# Robot2.net
KiCad netlist of a schematic drawn in EAGLE
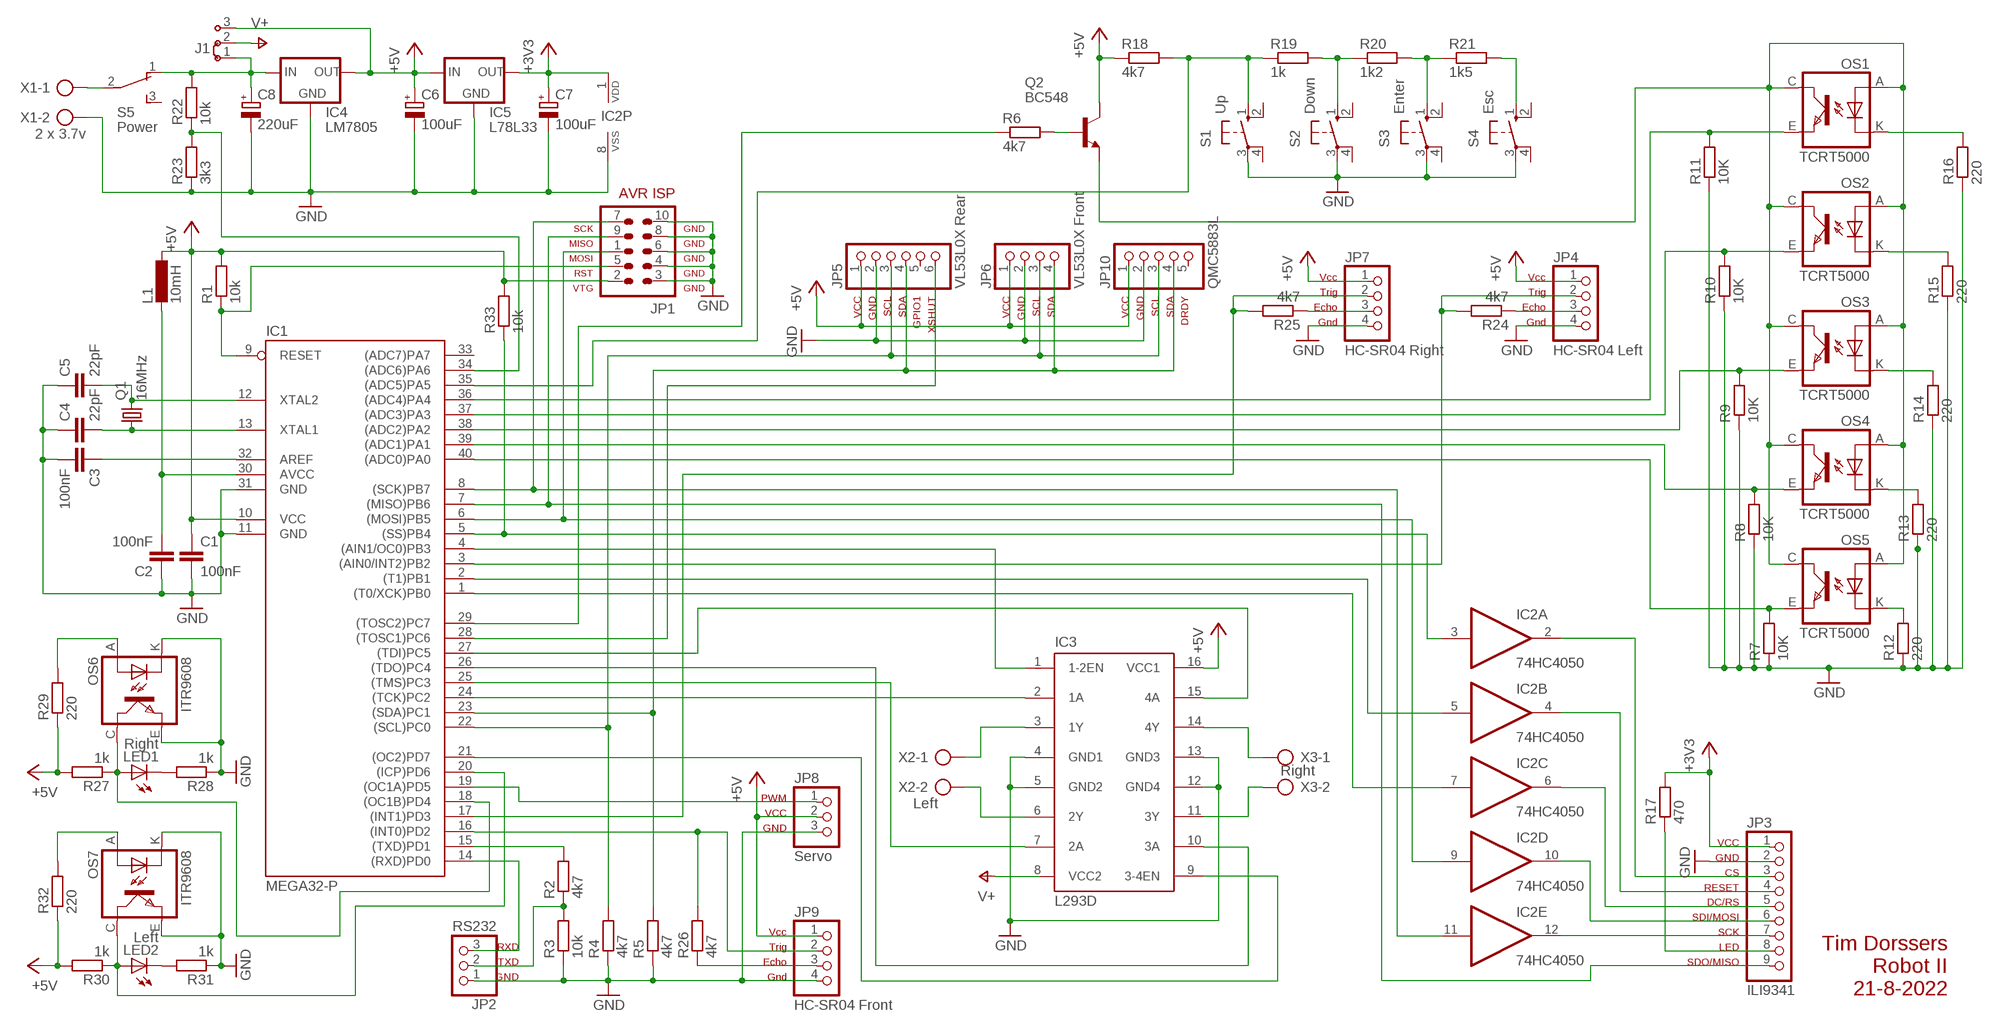
[diagram p0: schematic, sheet 1]

(export (version "E")
  (design (tool "Eeschema 10.0.6"))
  (components
    (comp (ref "C1")
      (value "100nF")
      (footprint "eagle-import:C050-025X075")
      (libsource (lib "eagle-import") (part "C-EU050-025X075"))
    )
    (comp (ref "C2")
      (value "100nF")
      (footprint "eagle-import:C050-025X075")
      (libsource (lib "eagle-import") (part "C-EU050-025X075"))
    )
    (comp (ref "C3")
      (value "100nF")
      (footprint "eagle-import:C050-025X075")
      (libsource (lib "eagle-import") (part "C-EU050-025X075"))
    )
    (comp (ref "C4")
      (value "22pF")
      (footprint "eagle-import:C025-024X044")
      (libsource (lib "eagle-import") (part "C-EU025-024X044"))
    )
    (comp (ref "C5")
      (value "22pF")
      (footprint "eagle-import:C025-024X044")
      (libsource (lib "eagle-import") (part "C-EU025-024X044"))
    )
    (comp (ref "C6")
      (value "100uF")
      (footprint "eagle-import:B45181A")
      (libsource (lib "eagle-import") (part "CPOL-EUB45181A"))
    )
    (comp (ref "C7")
      (value "100uF")
      (footprint "eagle-import:B45181A")
      (libsource (lib "eagle-import") (part "CPOL-EUB45181A"))
    )
    (comp (ref "C8")
      (value "220uF")
      (footprint "eagle-import:B45181A")
      (libsource (lib "eagle-import") (part "CPOL-EUB45181A"))
    )
    (comp (ref "IC1")
      (value "MEGA32-P")
      (footprint "eagle-import:DIL40")
      (fields (field (name "MPN") "ATMEGA32-16PU"))
      (libsource (lib "eagle-import") (part "MEGA32-P"))
    )
    (comp (ref "IC2")
      (value "74HC4050")
      (footprint "eagle-import:DIL16")
      (libsource (lib "eagle-import") (part "4050N"))
    )
    (comp (ref "IC3")
      (value "L293D")
      (footprint "eagle-import:DIL16")
      (libsource (lib "eagle-import") (part "L293D"))
    )
    (comp (ref "IC4")
      (value "LM7805")
      (footprint "eagle-import:78XXL")
      (libsource (lib "eagle-import") (part "78XXL"))
    )
    (comp (ref "IC5")
      (value "L78L33")
      (footprint "eagle-import:78LXX")
      (libsource (lib "eagle-import") (part "78LXX"))
    )
    (comp (ref "J1")
      (value "J2X2MM")
      (footprint "eagle-import:04C")
      (libsource (lib "eagle-import") (part "J2X2MM"))
    )
    (comp (ref "JP1")
      (value "AVR-ISP-10")
      (footprint "eagle-import:AVR-ISP-10")
      (libsource (lib "eagle-import") (part "AVR-ISP-10"))
    )
    (comp (ref "JP2")
      (value "RS232")
      (footprint "eagle-import:1X03")
      (libsource (lib "eagle-import") (part "PINHD-1X3"))
    )
    (comp (ref "JP3")
      (value "ILI9341")
      (footprint "eagle-import:1X09")
      (libsource (lib "eagle-import") (part "PINHD-1X9"))
    )
    (comp (ref "JP4")
      (value "HC-SR04 Left")
      (footprint "eagle-import:1X04")
      (libsource (lib "eagle-import") (part "PINHD-1X4"))
    )
    (comp (ref "JP5")
      (value "VL53L0X Rear")
      (footprint "eagle-import:1X06")
      (libsource (lib "eagle-import") (part "PINHD-1X6"))
    )
    (comp (ref "JP6")
      (value "VL53L0X Front")
      (footprint "eagle-import:1X04")
      (libsource (lib "eagle-import") (part "PINHD-1X4"))
    )
    (comp (ref "JP7")
      (value "HC-SR04 Right")
      (footprint "eagle-import:1X04")
      (libsource (lib "eagle-import") (part "PINHD-1X4"))
    )
    (comp (ref "JP8")
      (value "Servo")
      (footprint "eagle-import:1X03")
      (libsource (lib "eagle-import") (part "PINHD-1X3"))
    )
    (comp (ref "JP9")
      (value "HC-SR04 Front")
      (footprint "eagle-import:1X04")
      (libsource (lib "eagle-import") (part "PINHD-1X4"))
    )
    (comp (ref "JP10")
      (value "QMC5883L")
      (footprint "eagle-import:1X05")
      (libsource (lib "eagle-import") (part "PINHD-1X5"))
    )
    (comp (ref "L1")
      (value "10mH")
      (footprint "eagle-import:0207_10")
      (libsource (lib "eagle-import") (part "L-EU0207/10"))
    )
    (comp (ref "LED1")
      (value "Right")
      (footprint "eagle-import:LED5MM")
      (libsource (lib "eagle-import") (part "LED5MM"))
    )
    (comp (ref "LED2")
      (value "Left")
      (footprint "eagle-import:LED5MM")
      (libsource (lib "eagle-import") (part "LED5MM"))
    )
    (comp (ref "OS1")
      (value "TCRT5000")
      (footprint "eagle-import:TCRT5000")
      (libsource (lib "eagle-import") (part "TCRT5000"))
    )
    (comp (ref "OS2")
      (value "TCRT5000")
      (footprint "eagle-import:TCRT5000")
      (libsource (lib "eagle-import") (part "TCRT5000"))
    )
    (comp (ref "OS3")
      (value "TCRT5000")
      (footprint "eagle-import:TCRT5000")
      (libsource (lib "eagle-import") (part "TCRT5000"))
    )
    (comp (ref "OS4")
      (value "TCRT5000")
      (footprint "eagle-import:TCRT5000")
      (libsource (lib "eagle-import") (part "TCRT5000"))
    )
    (comp (ref "OS5")
      (value "TCRT5000")
      (footprint "eagle-import:TCRT5000")
      (libsource (lib "eagle-import") (part "TCRT5000"))
    )
    (comp (ref "OS6")
      (value "ITR9608")
      (footprint "eagle-import:TCRT5000")
      (libsource (lib "eagle-import") (part "TCRT5000"))
    )
    (comp (ref "OS7")
      (value "ITR9608")
      (footprint "eagle-import:TCRT5000")
      (libsource (lib "eagle-import") (part "TCRT5000"))
    )
    (comp (ref "Q1")
      (value "16MHz")
      (footprint "eagle-import:HC49U-V")
      (libsource (lib "eagle-import") (part "CRYSTALHC49U-V"))
    )
    (comp (ref "Q2")
      (value "BC548")
      (footprint "eagle-import:TO92-EBC")
      (libsource (lib "eagle-import") (part "BC548"))
    )
    (comp (ref "R1")
      (value "10k")
      (footprint "eagle-import:0207_2V")
      (libsource (lib "eagle-import") (part "R-EU_0207/2V"))
    )
    (comp (ref "R2")
      (value "4k7")
      (footprint "eagle-import:0207_2V")
      (libsource (lib "eagle-import") (part "R-EU_0207/2V"))
    )
    (comp (ref "R3")
      (value "10k")
      (footprint "eagle-import:0207_2V")
      (libsource (lib "eagle-import") (part "R-EU_0207/2V"))
    )
    (comp (ref "R4")
      (value "4k7")
      (footprint "eagle-import:0207_2V")
      (libsource (lib "eagle-import") (part "R-EU_0207/2V"))
    )
    (comp (ref "R5")
      (value "4k7")
      (footprint "eagle-import:0207_2V")
      (libsource (lib "eagle-import") (part "R-EU_0207/2V"))
    )
    (comp (ref "R6")
      (value "4k7")
      (footprint "eagle-import:0207_2V")
      (libsource (lib "eagle-import") (part "R-EU_0207/2V"))
    )
    (comp (ref "R7")
      (value "10K")
      (footprint "eagle-import:0204_7")
      (libsource (lib "eagle-import") (part "resistor_R-EU_0204/7"))
    )
    (comp (ref "R8")
      (value "10K")
      (footprint "eagle-import:0204_7")
      (libsource (lib "eagle-import") (part "resistor_R-EU_0204/7"))
    )
    (comp (ref "R9")
      (value "10K")
      (footprint "eagle-import:0204_7")
      (libsource (lib "eagle-import") (part "resistor_R-EU_0204/7"))
    )
    (comp (ref "R10")
      (value "10K")
      (footprint "eagle-import:0204_7")
      (libsource (lib "eagle-import") (part "resistor_R-EU_0204/7"))
    )
    (comp (ref "R11")
      (value "10K")
      (footprint "eagle-import:0204_7")
      (libsource (lib "eagle-import") (part "resistor_R-EU_0204/7"))
    )
    (comp (ref "R12")
      (value "220")
      (footprint "eagle-import:0204_7")
      (libsource (lib "eagle-import") (part "resistor_R-EU_0204/7"))
    )
    (comp (ref "R13")
      (value "220")
      (footprint "eagle-import:0204_7")
      (libsource (lib "eagle-import") (part "resistor_R-EU_0204/7"))
    )
    (comp (ref "R14")
      (value "220")
      (footprint "eagle-import:0204_7")
      (libsource (lib "eagle-import") (part "resistor_R-EU_0204/7"))
    )
    (comp (ref "R15")
      (value "220")
      (footprint "eagle-import:0204_7")
      (libsource (lib "eagle-import") (part "resistor_R-EU_0204/7"))
    )
    (comp (ref "R16")
      (value "220")
      (footprint "eagle-import:0204_7")
      (libsource (lib "eagle-import") (part "resistor_R-EU_0204/7"))
    )
    (comp (ref "R17")
      (value "470")
      (footprint "eagle-import:0207_2V")
      (libsource (lib "eagle-import") (part "R-EU_0207/2V"))
    )
    (comp (ref "R18")
      (value "4k7")
      (footprint "eagle-import:0207_2V")
      (libsource (lib "eagle-import") (part "R-EU_0207/2V"))
    )
    (comp (ref "R19")
      (value "1k")
      (footprint "eagle-import:0207_2V")
      (libsource (lib "eagle-import") (part "R-EU_0207/2V"))
    )
    (comp (ref "R20")
      (value "1k2")
      (footprint "eagle-import:0207_2V")
      (libsource (lib "eagle-import") (part "R-EU_0207/2V"))
    )
    (comp (ref "R21")
      (value "1k5")
      (footprint "eagle-import:0207_2V")
      (libsource (lib "eagle-import") (part "R-EU_0207/2V"))
    )
    (comp (ref "R22")
      (value "10k")
      (footprint "eagle-import:0207_2V")
      (libsource (lib "eagle-import") (part "R-EU_0207/2V"))
    )
    (comp (ref "R23")
      (value "3k3")
      (footprint "eagle-import:0207_2V")
      (libsource (lib "eagle-import") (part "R-EU_0207/2V"))
    )
    (comp (ref "R24")
      (value "4k7")
      (footprint "eagle-import:0207_2V")
      (libsource (lib "eagle-import") (part "R-EU_0207/2V"))
    )
    (comp (ref "R25")
      (value "4k7")
      (footprint "eagle-import:0207_2V")
      (libsource (lib "eagle-import") (part "R-EU_0207/2V"))
    )
    (comp (ref "R26")
      (value "4k7")
      (footprint "eagle-import:0207_2V")
      (libsource (lib "eagle-import") (part "R-EU_0207/2V"))
    )
    (comp (ref "R27")
      (value "1k")
      (footprint "eagle-import:0207_2V")
      (libsource (lib "eagle-import") (part "R-EU_0207/2V"))
    )
    (comp (ref "R28")
      (value "1k")
      (footprint "eagle-import:0207_2V")
      (libsource (lib "eagle-import") (part "R-EU_0207/2V"))
    )
    (comp (ref "R29")
      (value "220")
      (footprint "eagle-import:0207_2V")
      (libsource (lib "eagle-import") (part "R-EU_0207/2V"))
    )
    (comp (ref "R30")
      (value "1k")
      (footprint "eagle-import:0207_2V")
      (libsource (lib "eagle-import") (part "R-EU_0207/2V"))
    )
    (comp (ref "R31")
      (value "1k")
      (footprint "eagle-import:0207_2V")
      (libsource (lib "eagle-import") (part "R-EU_0207/2V"))
    )
    (comp (ref "R32")
      (value "220")
      (footprint "eagle-import:0207_2V")
      (libsource (lib "eagle-import") (part "R-EU_0207/2V"))
    )
    (comp (ref "R33")
      (value "10k")
      (footprint "eagle-import:0207_2V")
      (libsource (lib "eagle-import") (part "R-EU_0207/2V"))
    )
    (comp (ref "S1")
      (value "Up")
      (footprint "eagle-import:B3F-10XX")
      (fields (field (name "MPN") "B3F-1000"))
      (libsource (lib "eagle-import") (part "10-XX"))
    )
    (comp (ref "S2")
      (value "Down")
      (footprint "eagle-import:B3F-10XX")
      (fields (field (name "MPN") "B3F-1000"))
      (libsource (lib "eagle-import") (part "10-XX"))
    )
    (comp (ref "S3")
      (value "Enter")
      (footprint "eagle-import:B3F-10XX")
      (fields (field (name "MPN") "B3F-1000"))
      (libsource (lib "eagle-import") (part "10-XX"))
    )
    (comp (ref "S4")
      (value "Esc")
      (footprint "eagle-import:B3F-10XX")
      (fields (field (name "MPN") "B3F-1000"))
      (libsource (lib "eagle-import") (part "10-XX"))
    )
    (comp (ref "S5")
      (value "Power")
      (footprint "eagle-import:TL3XPO")
      (libsource (lib "eagle-import") (part "TL36PO"))
    )
    (comp (ref "X1")
      (value "2 x 3.7v")
      (footprint "eagle-import:AK300_2")
      (libsource (lib "eagle-import") (part "AK300/2"))
    )
    (comp (ref "X2")
      (value "Left")
      (footprint "eagle-import:AK300_2")
      (libsource (lib "eagle-import") (part "AK300/2"))
    )
    (comp (ref "X3")
      (value "Right")
      (footprint "eagle-import:AK300_2")
      (libsource (lib "eagle-import") (part "AK300/2"))
    )
  )
  (nets
    (net (code "1") (name "+3V3") (class "Default")
      (node (ref "C7") (pin "+") (pinfunction "+_+") (pintype "passive"))
      (node (ref "IC2") (pin "1") (pinfunction "VDD_1") (pintype "power_in"))
      (node (ref "IC5") (pin "OUT") (pinfunction "OUT_OUT") (pintype "passive"))
      (node (ref "JP3") (pin "1") (pinfunction "1_1") (pintype "passive"))
      (node (ref "R17") (pin "2") (pinfunction "2_2") (pintype "passive"))
    )
    (net (code "2") (name "+5V") (class "Default")
      (node (ref "C1") (pin "1") (pinfunction "1_1") (pintype "passive"))
      (node (ref "C6") (pin "+") (pinfunction "+_+") (pintype "passive"))
      (node (ref "IC1") (pin "10") (pinfunction "VCC_10") (pintype "power_in"))
      (node (ref "IC3") (pin "16") (pinfunction "VCC1_16") (pintype "power_in"))
      (node (ref "IC4") (pin "OUT") (pinfunction "OUT_OUT") (pintype "passive"))
      (node (ref "IC5") (pin "IN") (pinfunction "IN_IN") (pintype "input"))
      (node (ref "J1") (pin "3") (pinfunction "3_3") (pintype "passive"))
      (node (ref "JP1") (pin "2") (pinfunction "2_2") (pintype "passive"))
      (node (ref "JP10") (pin "1") (pinfunction "1_1") (pintype "passive"))
      (node (ref "JP4") (pin "1") (pinfunction "1_1") (pintype "passive"))
      (node (ref "JP5") (pin "1") (pinfunction "1_1") (pintype "passive"))
      (node (ref "JP6") (pin "1") (pinfunction "1_1") (pintype "passive"))
      (node (ref "JP7") (pin "1") (pinfunction "1_1") (pintype "passive"))
      (node (ref "JP8") (pin "2") (pinfunction "2_2") (pintype "passive"))
      (node (ref "JP9") (pin "1") (pinfunction "1_1") (pintype "passive"))
      (node (ref "L1") (pin "1") (pinfunction "1_1") (pintype "passive"))
      (node (ref "Q2") (pin "C") (pinfunction "C_C") (pintype "passive"))
      (node (ref "R1") (pin "2") (pinfunction "2_2") (pintype "passive"))
      (node (ref "R18") (pin "1") (pinfunction "1_1") (pintype "passive"))
      (node (ref "R27") (pin "2") (pinfunction "2_2") (pintype "passive"))
      (node (ref "R29") (pin "1") (pinfunction "1_1") (pintype "passive"))
      (node (ref "R30") (pin "2") (pinfunction "2_2") (pintype "passive"))
      (node (ref "R32") (pin "1") (pinfunction "1_1") (pintype "passive"))
      (node (ref "R33") (pin "2") (pinfunction "2_2") (pintype "passive"))
    )
    (net (code "3") (name "/VCC2") (class "Default")
      (node (ref "IC3") (pin "8") (pinfunction "VCC2_8") (pintype "power_in"))
    )
    (net (code "4") (name "GND") (class "Default")
      (node (ref "C1") (pin "2") (pinfunction "2_2") (pintype "passive"))
      (node (ref "C2") (pin "1") (pinfunction "1_1") (pintype "passive"))
      (node (ref "C3") (pin "2") (pinfunction "2_2") (pintype "passive"))
      (node (ref "C4") (pin "1") (pinfunction "1_1") (pintype "passive"))
      (node (ref "C5") (pin "1") (pinfunction "1_1") (pintype "passive"))
      (node (ref "C6") (pin "-") (pinfunction "-_-") (pintype "passive"))
      (node (ref "C7") (pin "-") (pinfunction "-_-") (pintype "passive"))
      (node (ref "C8") (pin "-") (pinfunction "-_-") (pintype "passive"))
      (node (ref "IC1") (pin "11") (pinfunction "GND_11") (pintype "power_in"))
      (node (ref "IC1") (pin "31") (pinfunction "GND_31") (pintype "power_in"))
      (node (ref "IC2") (pin "8") (pinfunction "VSS_8") (pintype "power_in"))
      (node (ref "IC3") (pin "12") (pinfunction "GND4_12") (pintype "power_in"))
      (node (ref "IC3") (pin "13") (pinfunction "GND3_13") (pintype "power_in"))
      (node (ref "IC3") (pin "4") (pinfunction "GND1_4") (pintype "power_in"))
      (node (ref "IC3") (pin "5") (pinfunction "GND2_5") (pintype "power_in"))
      (node (ref "IC4") (pin "GND") (pinfunction "GND_GND") (pintype "input"))
      (node (ref "IC5") (pin "GND") (pinfunction "GND_GND") (pintype "input"))
      (node (ref "JP1") (pin "10") (pinfunction "10_10") (pintype "passive"))
      (node (ref "JP1") (pin "3") (pinfunction "3_3") (pintype "passive"))
      (node (ref "JP1") (pin "4") (pinfunction "4_4") (pintype "passive"))
      (node (ref "JP1") (pin "6") (pinfunction "6_6") (pintype "passive"))
      (node (ref "JP1") (pin "8") (pinfunction "8_8") (pintype "passive"))
      (node (ref "JP10") (pin "2") (pinfunction "2_2") (pintype "passive"))
      (node (ref "JP2") (pin "1") (pinfunction "1_1") (pintype "passive"))
      (node (ref "JP3") (pin "2") (pinfunction "2_2") (pintype "passive"))
      (node (ref "JP4") (pin "4") (pinfunction "4_4") (pintype "passive"))
      (node (ref "JP5") (pin "2") (pinfunction "2_2") (pintype "passive"))
      (node (ref "JP6") (pin "2") (pinfunction "2_2") (pintype "passive"))
      (node (ref "JP7") (pin "4") (pinfunction "4_4") (pintype "passive"))
      (node (ref "JP8") (pin "3") (pinfunction "3_3") (pintype "passive"))
      (node (ref "JP9") (pin "4") (pinfunction "4_4") (pintype "passive"))
      (node (ref "OS6") (pin "E") (pinfunction "EMITTER_E") (pintype "passive"))
      (node (ref "OS6") (pin "K") (pinfunction "CATHODE_K") (pintype "passive"))
      (node (ref "OS7") (pin "E") (pinfunction "EMITTER_E") (pintype "passive"))
      (node (ref "OS7") (pin "K") (pinfunction "CATHODE_K") (pintype "passive"))
      (node (ref "R10") (pin "1") (pinfunction "1_1") (pintype "passive"))
      (node (ref "R11") (pin "1") (pinfunction "1_1") (pintype "passive"))
      (node (ref "R12") (pin "1") (pinfunction "1_1") (pintype "passive"))
      (node (ref "R13") (pin "1") (pinfunction "1_1") (pintype "passive"))
      (node (ref "R14") (pin "1") (pinfunction "1_1") (pintype "passive"))
      (node (ref "R15") (pin "1") (pinfunction "1_1") (pintype "passive"))
      (node (ref "R16") (pin "1") (pinfunction "1_1") (pintype "passive"))
      (node (ref "R23") (pin "1") (pinfunction "1_1") (pintype "passive"))
      (node (ref "R28") (pin "1") (pinfunction "1_1") (pintype "passive"))
      (node (ref "R3") (pin "1") (pinfunction "1_1") (pintype "passive"))
      (node (ref "R31") (pin "1") (pinfunction "1_1") (pintype "passive"))
      (node (ref "R4") (pin "1") (pinfunction "1_1") (pintype "passive"))
      (node (ref "R5") (pin "1") (pinfunction "1_1") (pintype "passive"))
      (node (ref "R7") (pin "1") (pinfunction "1_1") (pintype "passive"))
      (node (ref "R8") (pin "1") (pinfunction "1_1") (pintype "passive"))
      (node (ref "R9") (pin "1") (pinfunction "1_1") (pintype "passive"))
      (node (ref "S1") (pin "3") (pinfunction "P_3") (pintype "passive"))
      (node (ref "S2") (pin "3") (pinfunction "P_3") (pintype "passive"))
      (node (ref "S3") (pin "3") (pinfunction "P_3") (pintype "passive"))
      (node (ref "S4") (pin "3") (pinfunction "P_3") (pintype "passive"))
      (node (ref "X1") (pin "2") (pinfunction "KL_2") (pintype "passive"))
    )
    (net (code "5") (name "Net-(IC1-(ADC0)PA0)") (class "Default")
      (node (ref "IC1") (pin "40") (pinfunction "(ADC0)PA0_40") (pintype "bidirectional"))
      (node (ref "OS5") (pin "E") (pinfunction "EMITTER_E") (pintype "passive"))
      (node (ref "R7") (pin "2") (pinfunction "2_2") (pintype "passive"))
    )
    (net (code "6") (name "Net-(IC1-(ADC1)PA1)") (class "Default")
      (node (ref "IC1") (pin "39") (pinfunction "(ADC1)PA1_39") (pintype "bidirectional"))
      (node (ref "OS4") (pin "E") (pinfunction "EMITTER_E") (pintype "passive"))
      (node (ref "R8") (pin "2") (pinfunction "2_2") (pintype "passive"))
    )
    (net (code "7") (name "Net-(IC1-(ADC2)PA2)") (class "Default")
      (node (ref "IC1") (pin "38") (pinfunction "(ADC2)PA2_38") (pintype "bidirectional"))
      (node (ref "OS3") (pin "E") (pinfunction "EMITTER_E") (pintype "passive"))
      (node (ref "R9") (pin "2") (pinfunction "2_2") (pintype "passive"))
    )
    (net (code "8") (name "Net-(IC1-(ADC3)PA3)") (class "Default")
      (node (ref "IC1") (pin "37") (pinfunction "(ADC3)PA3_37") (pintype "bidirectional"))
      (node (ref "OS2") (pin "E") (pinfunction "EMITTER_E") (pintype "passive"))
      (node (ref "R10") (pin "2") (pinfunction "2_2") (pintype "passive"))
    )
    (net (code "9") (name "Net-(IC1-(ADC4)PA4)") (class "Default")
      (node (ref "IC1") (pin "36") (pinfunction "(ADC4)PA4_36") (pintype "bidirectional"))
      (node (ref "OS1") (pin "E") (pinfunction "EMITTER_E") (pintype "passive"))
      (node (ref "R11") (pin "2") (pinfunction "2_2") (pintype "passive"))
    )
    (net (code "10") (name "Net-(IC1-(ADC5)PA5)") (class "Default")
      (node (ref "IC1") (pin "35") (pinfunction "(ADC5)PA5_35") (pintype "bidirectional"))
      (node (ref "R18") (pin "2") (pinfunction "2_2") (pintype "passive"))
      (node (ref "R19") (pin "1") (pinfunction "1_1") (pintype "passive"))
      (node (ref "S1") (pin "1") (pinfunction "S_1") (pintype "passive"))
    )
    (net (code "11") (name "Net-(IC1-(ADC6)PA6)") (class "Default")
      (node (ref "IC1") (pin "34") (pinfunction "(ADC6)PA6_34") (pintype "bidirectional"))
      (node (ref "R22") (pin "1") (pinfunction "1_1") (pintype "passive"))
      (node (ref "R23") (pin "2") (pinfunction "2_2") (pintype "passive"))
    )
    (net (code "12") (name "Net-(IC1-(AIN0{slash}INT2)PB2)") (class "Default")
      (node (ref "IC1") (pin "3") (pinfunction "(AIN0/INT2)PB2_3") (pintype "bidirectional"))
      (node (ref "JP4") (pin "2") (pinfunction "2_2") (pintype "passive"))
      (node (ref "R24") (pin "2") (pinfunction "2_2") (pintype "passive"))
    )
    (net (code "13") (name "Net-(IC1-(AIN1{slash}OC0)PB3)") (class "Default")
      (node (ref "IC1") (pin "4") (pinfunction "(AIN1/OC0)PB3_4") (pintype "bidirectional"))
      (node (ref "IC3") (pin "1") (pinfunction "1-2EN_1") (pintype "input"))
    )
    (net (code "14") (name "Net-(IC1-(ICP)PD6)") (class "Default")
      (node (ref "IC1") (pin "20") (pinfunction "(ICP)PD6_20") (pintype "bidirectional"))
      (node (ref "LED2") (pin "A") (pinfunction "A_A") (pintype "passive"))
      (node (ref "OS7") (pin "C") (pinfunction "COLLECTOR_C") (pintype "passive"))
      (node (ref "R30") (pin "1") (pinfunction "1_1") (pintype "passive"))
    )
    (net (code "15") (name "Net-(IC1-(INT0)PD2)") (class "Default")
      (node (ref "IC1") (pin "16") (pinfunction "(INT0)PD2_16") (pintype "bidirectional"))
      (node (ref "JP9") (pin "2") (pinfunction "2_2") (pintype "passive"))
      (node (ref "R26") (pin "2") (pinfunction "2_2") (pintype "passive"))
    )
    (net (code "16") (name "Net-(IC1-(INT1)PD3)") (class "Default")
      (node (ref "IC1") (pin "17") (pinfunction "(INT1)PD3_17") (pintype "bidirectional"))
      (node (ref "JP7") (pin "2") (pinfunction "2_2") (pintype "passive"))
      (node (ref "R25") (pin "2") (pinfunction "2_2") (pintype "passive"))
    )
    (net (code "17") (name "Net-(IC1-(MISO)PB6)") (class "Default")
      (node (ref "IC1") (pin "7") (pinfunction "(MISO)PB6_7") (pintype "bidirectional"))
      (node (ref "JP1") (pin "9") (pinfunction "9_9") (pintype "passive"))
      (node (ref "JP3") (pin "9") (pinfunction "9_9") (pintype "passive"))
    )
    (net (code "18") (name "Net-(IC1-(MOSI)PB5)") (class "Default")
      (node (ref "IC1") (pin "6") (pinfunction "(MOSI)PB5_6") (pintype "bidirectional"))
      (node (ref "IC2") (pin "9") (pinfunction "I_9") (pintype "input"))
      (node (ref "JP1") (pin "1") (pinfunction "1_1") (pintype "passive"))
    )
    (net (code "19") (name "Net-(IC1-(OC1A)PD5)") (class "Default")
      (node (ref "IC1") (pin "19") (pinfunction "(OC1A)PD5_19") (pintype "bidirectional"))
      (node (ref "JP8") (pin "1") (pinfunction "1_1") (pintype "passive"))
    )
    (net (code "20") (name "Net-(IC1-(OC1B)PD4)") (class "Default")
      (node (ref "IC1") (pin "18") (pinfunction "(OC1B)PD4_18") (pintype "bidirectional"))
      (node (ref "LED1") (pin "A") (pinfunction "A_A") (pintype "passive"))
      (node (ref "OS6") (pin "C") (pinfunction "COLLECTOR_C") (pintype "passive"))
      (node (ref "R27") (pin "1") (pinfunction "1_1") (pintype "passive"))
    )
    (net (code "21") (name "Net-(IC1-(OC2)PD7)") (class "Default")
      (node (ref "IC1") (pin "21") (pinfunction "(OC2)PD7_21") (pintype "bidirectional"))
      (node (ref "IC3") (pin "9") (pinfunction "3-4EN_9") (pintype "input"))
    )
    (net (code "22") (name "Net-(IC1-(RXD)PD0)") (class "Default")
      (node (ref "IC1") (pin "14") (pinfunction "(RXD)PD0_14") (pintype "bidirectional"))
      (node (ref "JP2") (pin "3") (pinfunction "3_3") (pintype "passive"))
    )
    (net (code "23") (name "Net-(IC1-(SCK)PB7)") (class "Default")
      (node (ref "IC1") (pin "8") (pinfunction "(SCK)PB7_8") (pintype "bidirectional"))
      (node (ref "IC2") (pin "11") (pinfunction "I_11") (pintype "input"))
      (node (ref "JP1") (pin "7") (pinfunction "7_7") (pintype "passive"))
    )
    (net (code "24") (name "Net-(IC1-(SCL)PC0)") (class "Default")
      (node (ref "IC1") (pin "22") (pinfunction "(SCL)PC0_22") (pintype "bidirectional"))
      (node (ref "JP10") (pin "3") (pinfunction "3_3") (pintype "passive"))
      (node (ref "JP5") (pin "3") (pinfunction "3_3") (pintype "passive"))
      (node (ref "JP6") (pin "3") (pinfunction "3_3") (pintype "passive"))
      (node (ref "R4") (pin "2") (pinfunction "2_2") (pintype "passive"))
    )
    (net (code "25") (name "Net-(IC1-(SDA)PC1)") (class "Default")
      (node (ref "IC1") (pin "23") (pinfunction "(SDA)PC1_23") (pintype "bidirectional"))
      (node (ref "JP10") (pin "4") (pinfunction "4_4") (pintype "passive"))
      (node (ref "JP5") (pin "4") (pinfunction "4_4") (pintype "passive"))
      (node (ref "JP6") (pin "4") (pinfunction "4_4") (pintype "passive"))
      (node (ref "R5") (pin "2") (pinfunction "2_2") (pintype "passive"))
    )
    (net (code "26") (name "Net-(IC1-(SS)PB4)") (class "Default")
      (node (ref "IC1") (pin "5") (pinfunction "(SS)PB4_5") (pintype "bidirectional"))
      (node (ref "IC2") (pin "3") (pinfunction "I_3") (pintype "input"))
      (node (ref "R33") (pin "1") (pinfunction "1_1") (pintype "passive"))
    )
    (net (code "27") (name "Net-(IC1-(T0{slash}XCK)PB0)") (class "Default")
      (node (ref "IC1") (pin "1") (pinfunction "(T0/XCK)PB0_1") (pintype "bidirectional"))
      (node (ref "IC2") (pin "7") (pinfunction "I_7") (pintype "input"))
    )
    (net (code "28") (name "Net-(IC1-(T1)PB1)") (class "Default")
      (node (ref "IC1") (pin "2") (pinfunction "(T1)PB1_2") (pintype "bidirectional"))
      (node (ref "IC2") (pin "5") (pinfunction "I_5") (pintype "input"))
    )
    (net (code "29") (name "Net-(IC1-(TCK)PC2)") (class "Default")
      (node (ref "IC1") (pin "24") (pinfunction "(TCK)PC2_24") (pintype "bidirectional"))
      (node (ref "IC3") (pin "2") (pinfunction "1A_2") (pintype "input"))
    )
    (net (code "30") (name "Net-(IC1-(TDI)PC5)") (class "Default")
      (node (ref "IC1") (pin "27") (pinfunction "(TDI)PC5_27") (pintype "bidirectional"))
      (node (ref "IC3") (pin "15") (pinfunction "4A_15") (pintype "input"))
    )
    (net (code "31") (name "Net-(IC1-(TDO)PC4)") (class "Default")
      (node (ref "IC1") (pin "26") (pinfunction "(TDO)PC4_26") (pintype "bidirectional"))
      (node (ref "IC3") (pin "10") (pinfunction "3A_10") (pintype "input"))
    )
    (net (code "32") (name "Net-(IC1-(TMS)PC3)") (class "Default")
      (node (ref "IC1") (pin "25") (pinfunction "(TMS)PC3_25") (pintype "bidirectional"))
      (node (ref "IC3") (pin "7") (pinfunction "2A_7") (pintype "input"))
    )
    (net (code "33") (name "Net-(IC1-(TOSC1)PC6)") (class "Default")
      (node (ref "IC1") (pin "28") (pinfunction "(TOSC1)PC6_28") (pintype "bidirectional"))
      (node (ref "JP5") (pin "6") (pinfunction "6_6") (pintype "passive"))
    )
    (net (code "34") (name "Net-(IC1-(TOSC2)PC7)") (class "Default")
      (node (ref "IC1") (pin "29") (pinfunction "(TOSC2)PC7_29") (pintype "bidirectional"))
      (node (ref "R6") (pin "1") (pinfunction "1_1") (pintype "passive"))
    )
    (net (code "35") (name "Net-(IC1-(TXD)PD1)") (class "Default")
      (node (ref "IC1") (pin "15") (pinfunction "(TXD)PD1_15") (pintype "bidirectional"))
      (node (ref "R2") (pin "2") (pinfunction "2_2") (pintype "passive"))
    )
    (net (code "36") (name "Net-(IC1-AREF)") (class "Default")
      (node (ref "C3") (pin "1") (pinfunction "1_1") (pintype "passive"))
      (node (ref "IC1") (pin "32") (pinfunction "AREF_32") (pintype "passive"))
    )
    (net (code "37") (name "Net-(IC1-AVCC)") (class "Default")
      (node (ref "C2") (pin "2") (pinfunction "2_2") (pintype "passive"))
      (node (ref "IC1") (pin "30") (pinfunction "AVCC_30") (pintype "power_in"))
      (node (ref "L1") (pin "2") (pinfunction "2_2") (pintype "passive"))
    )
    (net (code "38") (name "Net-(IC1-RESET)") (class "Default")
      (node (ref "IC1") (pin "9") (pinfunction "RESET_9") (pintype "input"))
      (node (ref "JP1") (pin "5") (pinfunction "5_5") (pintype "passive"))
      (node (ref "R1") (pin "1") (pinfunction "1_1") (pintype "passive"))
    )
    (net (code "39") (name "Net-(IC1-XTAL1)") (class "Default")
      (node (ref "C4") (pin "2") (pinfunction "2_2") (pintype "passive"))
      (node (ref "IC1") (pin "13") (pinfunction "XTAL1_13") (pintype "bidirectional"))
      (node (ref "Q1") (pin "1") (pinfunction "1_1") (pintype "passive"))
    )
    (net (code "40") (name "Net-(IC1-XTAL2)") (class "Default")
      (node (ref "C5") (pin "2") (pinfunction "2_2") (pintype "passive"))
      (node (ref "IC1") (pin "12") (pinfunction "XTAL2_12") (pintype "bidirectional"))
      (node (ref "Q1") (pin "2") (pinfunction "2_2") (pintype "passive"))
    )
    (net (code "41") (name "Net-(IC2A-O)") (class "Default")
      (node (ref "IC2") (pin "2") (pinfunction "O_2") (pintype "output"))
      (node (ref "JP3") (pin "3") (pinfunction "3_3") (pintype "passive"))
    )
    (net (code "42") (name "Net-(IC2B-O)") (class "Default")
      (node (ref "IC2") (pin "4") (pinfunction "O_4") (pintype "output"))
      (node (ref "JP3") (pin "4") (pinfunction "4_4") (pintype "passive"))
    )
    (net (code "43") (name "Net-(IC2C-O)") (class "Default")
      (node (ref "IC2") (pin "6") (pinfunction "O_6") (pintype "output"))
      (node (ref "JP3") (pin "5") (pinfunction "5_5") (pintype "passive"))
    )
    (net (code "44") (name "Net-(IC2D-O)") (class "Default")
      (node (ref "IC2") (pin "10") (pinfunction "O_10") (pintype "output"))
      (node (ref "JP3") (pin "6") (pinfunction "6_6") (pintype "passive"))
    )
    (net (code "45") (name "Net-(IC2E-O)") (class "Default")
      (node (ref "IC2") (pin "12") (pinfunction "O_12") (pintype "output"))
      (node (ref "JP3") (pin "7") (pinfunction "7_7") (pintype "passive"))
    )
    (net (code "46") (name "Net-(IC3-1Y)") (class "Default")
      (node (ref "IC3") (pin "3") (pinfunction "1Y_3") (pintype "output"))
      (node (ref "X2") (pin "1") (pinfunction "KL_1") (pintype "passive"))
    )
    (net (code "47") (name "Net-(IC3-2Y)") (class "Default")
      (node (ref "IC3") (pin "6") (pinfunction "2Y_6") (pintype "output"))
      (node (ref "X2") (pin "2") (pinfunction "KL_2") (pintype "passive"))
    )
    (net (code "48") (name "Net-(IC3-3Y)") (class "Default")
      (node (ref "IC3") (pin "11") (pinfunction "3Y_11") (pintype "output"))
      (node (ref "X3") (pin "2") (pinfunction "KL_2") (pintype "passive"))
    )
    (net (code "49") (name "Net-(IC3-4Y)") (class "Default")
      (node (ref "IC3") (pin "14") (pinfunction "4Y_14") (pintype "output"))
      (node (ref "X3") (pin "1") (pinfunction "KL_1") (pintype "passive"))
    )
    (net (code "50") (name "Net-(JP2-Pad2)") (class "Default")
      (node (ref "JP2") (pin "2") (pinfunction "2_2") (pintype "passive"))
      (node (ref "R2") (pin "1") (pinfunction "1_1") (pintype "passive"))
      (node (ref "R3") (pin "2") (pinfunction "2_2") (pintype "passive"))
    )
    (net (code "51") (name "Net-(JP3-Pad8)") (class "Default")
      (node (ref "JP3") (pin "8") (pinfunction "8_8") (pintype "passive"))
      (node (ref "R17") (pin "1") (pinfunction "1_1") (pintype "passive"))
    )
    (net (code "52") (name "Net-(JP4-Pad3)") (class "Default")
      (node (ref "JP4") (pin "3") (pinfunction "3_3") (pintype "passive"))
      (node (ref "R24") (pin "1") (pinfunction "1_1") (pintype "passive"))
    )
    (net (code "53") (name "Net-(JP7-Pad3)") (class "Default")
      (node (ref "JP7") (pin "3") (pinfunction "3_3") (pintype "passive"))
      (node (ref "R25") (pin "1") (pinfunction "1_1") (pintype "passive"))
    )
    (net (code "54") (name "Net-(JP9-Pad3)") (class "Default")
      (node (ref "JP9") (pin "3") (pinfunction "3_3") (pintype "passive"))
      (node (ref "R26") (pin "1") (pinfunction "1_1") (pintype "passive"))
    )
    (net (code "55") (name "Net-(LED1-C)") (class "Default")
      (node (ref "LED1") (pin "K") (pinfunction "C_K") (pintype "passive"))
      (node (ref "R28") (pin "2") (pinfunction "2_2") (pintype "passive"))
    )
    (net (code "56") (name "Net-(LED2-C)") (class "Default")
      (node (ref "LED2") (pin "K") (pinfunction "C_K") (pintype "passive"))
      (node (ref "R31") (pin "2") (pinfunction "2_2") (pintype "passive"))
    )
    (net (code "57") (name "Net-(OS1-ANODE)") (class "Default")
      (node (ref "OS1") (pin "A") (pinfunction "ANODE_A") (pintype "passive"))
      (node (ref "OS1") (pin "C") (pinfunction "COLLECTOR_C") (pintype "passive"))
      (node (ref "OS2") (pin "A") (pinfunction "ANODE_A") (pintype "passive"))
      (node (ref "OS2") (pin "C") (pinfunction "COLLECTOR_C") (pintype "passive"))
      (node (ref "OS3") (pin "A") (pinfunction "ANODE_A") (pintype "passive"))
      (node (ref "OS3") (pin "C") (pinfunction "COLLECTOR_C") (pintype "passive"))
      (node (ref "OS4") (pin "A") (pinfunction "ANODE_A") (pintype "passive"))
      (node (ref "OS4") (pin "C") (pinfunction "COLLECTOR_C") (pintype "passive"))
      (node (ref "OS5") (pin "A") (pinfunction "ANODE_A") (pintype "passive"))
      (node (ref "OS5") (pin "C") (pinfunction "COLLECTOR_C") (pintype "passive"))
      (node (ref "Q2") (pin "E") (pinfunction "E_E") (pintype "passive"))
    )
    (net (code "58") (name "Net-(OS1-CATHODE)") (class "Default")
      (node (ref "OS1") (pin "K") (pinfunction "CATHODE_K") (pintype "passive"))
      (node (ref "R16") (pin "2") (pinfunction "2_2") (pintype "passive"))
    )
    (net (code "59") (name "Net-(OS2-CATHODE)") (class "Default")
      (node (ref "OS2") (pin "K") (pinfunction "CATHODE_K") (pintype "passive"))
      (node (ref "R15") (pin "2") (pinfunction "2_2") (pintype "passive"))
    )
    (net (code "60") (name "Net-(OS3-CATHODE)") (class "Default")
      (node (ref "OS3") (pin "K") (pinfunction "CATHODE_K") (pintype "passive"))
      (node (ref "R14") (pin "2") (pinfunction "2_2") (pintype "passive"))
    )
    (net (code "61") (name "Net-(OS4-CATHODE)") (class "Default")
      (node (ref "OS4") (pin "K") (pinfunction "CATHODE_K") (pintype "passive"))
      (node (ref "R13") (pin "2") (pinfunction "2_2") (pintype "passive"))
    )
    (net (code "62") (name "Net-(OS5-CATHODE)") (class "Default")
      (node (ref "OS5") (pin "K") (pinfunction "CATHODE_K") (pintype "passive"))
      (node (ref "R12") (pin "2") (pinfunction "2_2") (pintype "passive"))
    )
    (net (code "63") (name "Net-(OS6-ANODE)") (class "Default")
      (node (ref "OS6") (pin "A") (pinfunction "ANODE_A") (pintype "passive"))
      (node (ref "R29") (pin "2") (pinfunction "2_2") (pintype "passive"))
    )
    (net (code "64") (name "Net-(OS7-ANODE)") (class "Default")
      (node (ref "OS7") (pin "A") (pinfunction "ANODE_A") (pintype "passive"))
      (node (ref "R32") (pin "2") (pinfunction "2_2") (pintype "passive"))
    )
    (net (code "65") (name "Net-(Q2-PadB)") (class "Default")
      (node (ref "Q2") (pin "B") (pinfunction "B_B") (pintype "passive"))
      (node (ref "R6") (pin "2") (pinfunction "2_2") (pintype "passive"))
    )
    (net (code "66") (name "Net-(S2-S)") (class "Default")
      (node (ref "R19") (pin "2") (pinfunction "2_2") (pintype "passive"))
      (node (ref "R20") (pin "1") (pinfunction "1_1") (pintype "passive"))
      (node (ref "S2") (pin "1") (pinfunction "S_1") (pintype "passive"))
    )
    (net (code "67") (name "Net-(S3-S)") (class "Default")
      (node (ref "R20") (pin "2") (pinfunction "2_2") (pintype "passive"))
      (node (ref "R21") (pin "1") (pinfunction "1_1") (pintype "passive"))
      (node (ref "S3") (pin "1") (pinfunction "S_1") (pintype "passive"))
    )
    (net (code "68") (name "Net-(S4-S)") (class "Default")
      (node (ref "R21") (pin "2") (pinfunction "2_2") (pintype "passive"))
      (node (ref "S4") (pin "1") (pinfunction "S_1") (pintype "passive"))
    )
    (net (code "69") (name "Net-(S5-O)") (class "Default")
      (node (ref "C8") (pin "+") (pinfunction "+_+") (pintype "passive"))
      (node (ref "IC4") (pin "IN") (pinfunction "IN_IN") (pintype "input"))
      (node (ref "J1") (pin "1") (pinfunction "1_1") (pintype "passive"))
      (node (ref "R22") (pin "2") (pinfunction "2_2") (pintype "passive"))
      (node (ref "S5") (pin "1") (pinfunction "O_1") (pintype "passive"))
    )
    (net (code "70") (name "Net-(S5-P)") (class "Default")
      (node (ref "S5") (pin "2") (pinfunction "P_2") (pintype "passive"))
      (node (ref "X1") (pin "1") (pinfunction "KL_1") (pintype "passive"))
    )
    (net (code "71") (name "V+") (class "Default")
      (node (ref "J1") (pin "2") (pinfunction "2_2") (pintype "passive"))
    )
    (net (code "72") (name "unconnected-(IC1-(ADC7)PA7-Pad33)") (class "Default")
      (node (ref "IC1") (pin "33") (pinfunction "(ADC7)PA7_33") (pintype "bidirectional"))
    )
    (net (code "73") (name "unconnected-(JP5-Pad5)") (class "Default")
      (node (ref "JP5") (pin "5") (pinfunction "5_5") (pintype "passive"))
    )
    (net (code "74") (name "unconnected-(JP10-Pad5)") (class "Default")
      (node (ref "JP10") (pin "5") (pinfunction "5_5") (pintype "passive"))
    )
    (net (code "75") (name "unconnected-(S1-P1-Pad4)") (class "Default")
      (node (ref "S1") (pin "4") (pinfunction "P1_4") (pintype "passive"))
    )
    (net (code "76") (name "unconnected-(S1-S1-Pad2)") (class "Default")
      (node (ref "S1") (pin "2") (pinfunction "S1_2") (pintype "passive"))
    )
    (net (code "77") (name "unconnected-(S2-P1-Pad4)") (class "Default")
      (node (ref "S2") (pin "4") (pinfunction "P1_4") (pintype "passive"))
    )
    (net (code "78") (name "unconnected-(S2-S1-Pad2)") (class "Default")
      (node (ref "S2") (pin "2") (pinfunction "S1_2") (pintype "passive"))
    )
    (net (code "79") (name "unconnected-(S3-P1-Pad4)") (class "Default")
      (node (ref "S3") (pin "4") (pinfunction "P1_4") (pintype "passive"))
    )
    (net (code "80") (name "unconnected-(S3-S1-Pad2)") (class "Default")
      (node (ref "S3") (pin "2") (pinfunction "S1_2") (pintype "passive"))
    )
    (net (code "81") (name "unconnected-(S4-P1-Pad4)") (class "Default")
      (node (ref "S4") (pin "4") (pinfunction "P1_4") (pintype "passive"))
    )
    (net (code "82") (name "unconnected-(S4-S1-Pad2)") (class "Default")
      (node (ref "S4") (pin "2") (pinfunction "S1_2") (pintype "passive"))
    )
    (net (code "83") (name "unconnected-(S5-S-Pad3)") (class "Default")
      (node (ref "S5") (pin "3") (pinfunction "S_3") (pintype "passive"))
    )
  )
)
